# sy88932l_sampler.net
KiCad netlist of a schematic drawn in EAGLE
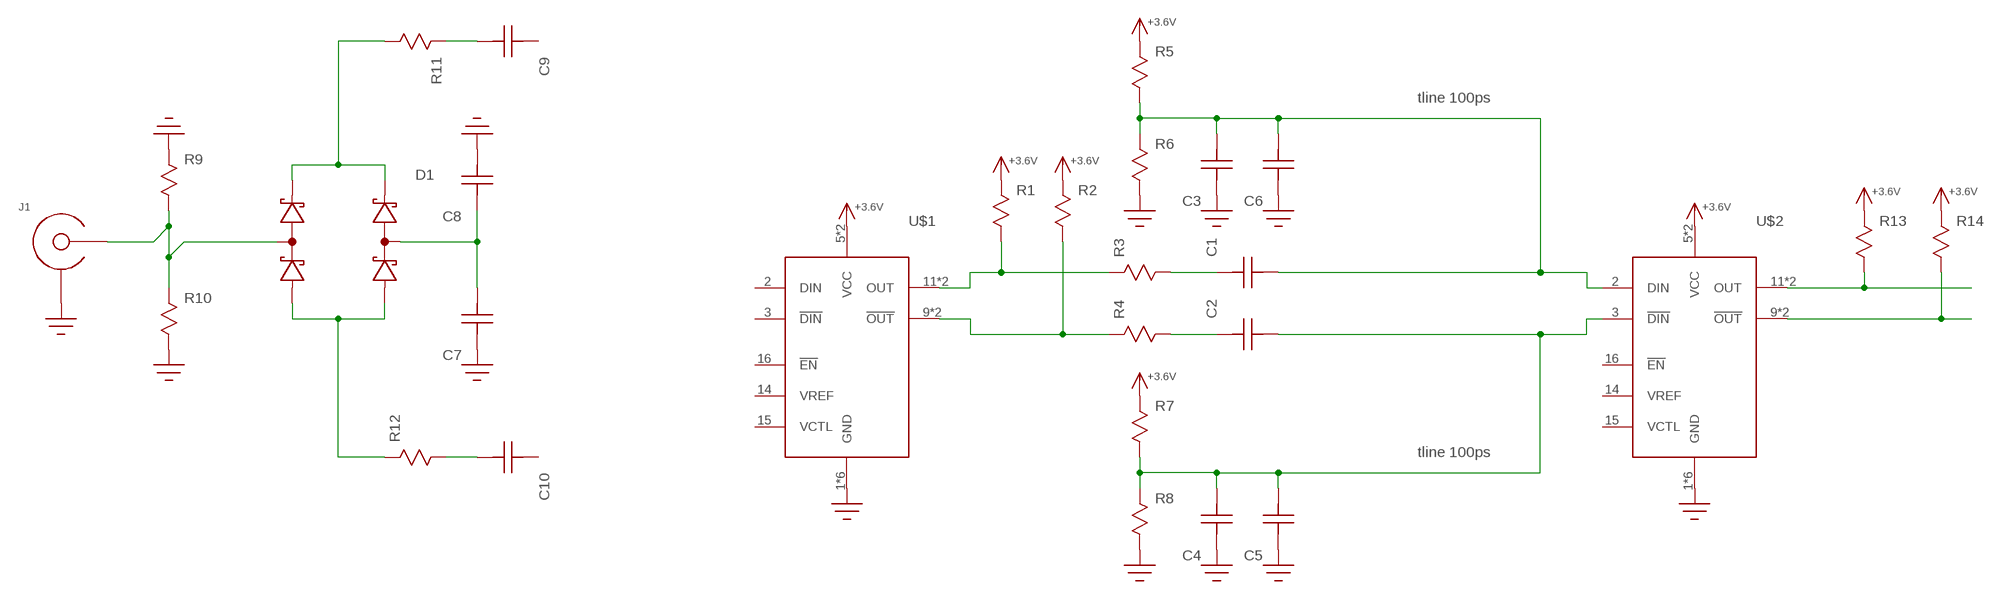
[diagram p0: schematic, sheet 1]

(export (version "E")
  (design (tool "Eeschema 10.0.6"))
  (components
    (comp (ref "C1")
      (value "C0603")
      (footprint "eagle-import:C0603")
      (libsource (lib "eagle-import") (part "C0603"))
    )
    (comp (ref "C2")
      (value "C0603")
      (footprint "eagle-import:C0603")
      (libsource (lib "eagle-import") (part "C0603"))
    )
    (comp (ref "C3")
      (value "C0603")
      (footprint "eagle-import:C0603")
      (libsource (lib "eagle-import") (part "C0603"))
    )
    (comp (ref "C4")
      (value "C0603")
      (footprint "eagle-import:C0603")
      (libsource (lib "eagle-import") (part "C0603"))
    )
    (comp (ref "C5") (value "C") (footprint "eagle-import:C0402") (libsource (lib "eagle-import") (part "C")))
    (comp (ref "C6") (value "C") (footprint "eagle-import:C0402") (libsource (lib "eagle-import") (part "C")))
    (comp (ref "C7") (value "C") (footprint "eagle-import:C0402") (libsource (lib "eagle-import") (part "C")))
    (comp (ref "C8") (value "C") (footprint "eagle-import:C0402") (libsource (lib "eagle-import") (part "C")))
    (comp (ref "C9") (value "C") (footprint "eagle-import:C0402") (libsource (lib "eagle-import") (part "C")))
    (comp (ref "C10")
      (value "C")
      (footprint "eagle-import:C0402")
      (libsource (lib "eagle-import") (part "C"))
    )
    (comp (ref "D1")
      (value "SMS3923-081")
      (footprint "eagle-import:SC-88")
      (libsource (lib "eagle-import") (part "SMS3923-081"))
    )
    (comp (ref "J1")
      (value "SMA_END_LAUNCH4L")
      (footprint "eagle-import:SMA_EDGE_LAUNCH")
      (libsource (lib "eagle-import") (part "SMA_END_LAUNCH4L"))
    )
    (comp (ref "R1")
      (value "R0603")
      (footprint "eagle-import:R0603")
      (libsource (lib "eagle-import") (part "R0603"))
    )
    (comp (ref "R2")
      (value "R0603")
      (footprint "eagle-import:R0603")
      (libsource (lib "eagle-import") (part "R0603"))
    )
    (comp (ref "R3")
      (value "R0603")
      (footprint "eagle-import:R0603")
      (libsource (lib "eagle-import") (part "R0603"))
    )
    (comp (ref "R4")
      (value "R0603")
      (footprint "eagle-import:R0603")
      (libsource (lib "eagle-import") (part "R0603"))
    )
    (comp (ref "R5")
      (value "R0603")
      (footprint "eagle-import:R0603")
      (libsource (lib "eagle-import") (part "R0603"))
    )
    (comp (ref "R6")
      (value "R0603")
      (footprint "eagle-import:R0603")
      (libsource (lib "eagle-import") (part "R0603"))
    )
    (comp (ref "R7")
      (value "R0603")
      (footprint "eagle-import:R0603")
      (libsource (lib "eagle-import") (part "R0603"))
    )
    (comp (ref "R8")
      (value "R0603")
      (footprint "eagle-import:R0603")
      (libsource (lib "eagle-import") (part "R0603"))
    )
    (comp (ref "R9")
      (value "R0603")
      (footprint "eagle-import:R0603")
      (libsource (lib "eagle-import") (part "R0603"))
    )
    (comp (ref "R10")
      (value "R0603")
      (footprint "eagle-import:R0603")
      (libsource (lib "eagle-import") (part "R0603"))
    )
    (comp (ref "R11")
      (value "R0603")
      (footprint "eagle-import:R0603")
      (libsource (lib "eagle-import") (part "R0603"))
    )
    (comp (ref "R12")
      (value "R0603")
      (footprint "eagle-import:R0603")
      (libsource (lib "eagle-import") (part "R0603"))
    )
    (comp (ref "R13")
      (value "R0603")
      (footprint "eagle-import:R0603")
      (libsource (lib "eagle-import") (part "R0603"))
    )
    (comp (ref "R14")
      (value "R0603")
      (footprint "eagle-import:R0603")
      (libsource (lib "eagle-import") (part "R0603"))
    )
    (comp (ref "U$1")
      (value "SY88932L")
      (footprint "eagle-import:TQFN16")
      (libsource (lib "eagle-import") (part "SY88932L"))
    )
    (comp (ref "U$2")
      (value "SY88932L")
      (footprint "eagle-import:TQFN16")
      (libsource (lib "eagle-import") (part "SY88932L"))
    )
  )
  (nets
    (net (code "1") (name "+3.6V") (class "Default")
      (node (ref "R1") (pin "P$1") (pinfunction "P$3_P$1") (pintype "bidirectional"))
      (node (ref "R13") (pin "P$1") (pinfunction "P$3_P$1") (pintype "bidirectional"))
      (node (ref "R14") (pin "P$1") (pinfunction "P$3_P$1") (pintype "bidirectional"))
      (node (ref "R2") (pin "P$1") (pinfunction "P$3_P$1") (pintype "bidirectional"))
      (node (ref "R5") (pin "P$1") (pinfunction "P$3_P$1") (pintype "bidirectional"))
      (node (ref "R7") (pin "P$1") (pinfunction "P$3_P$1") (pintype "bidirectional"))
      (node (ref "U$1") (pin "5") (pinfunction "VCC_5") (pintype "bidirectional"))
      (node (ref "U$1") (pin "6") (pinfunction "VCC_6") (pintype "bidirectional"))
      (node (ref "U$2") (pin "5") (pinfunction "VCC_5") (pintype "bidirectional"))
      (node (ref "U$2") (pin "6") (pinfunction "VCC_6") (pintype "bidirectional"))
    )
    (net (code "2") (name "GND") (class "Default")
      (node (ref "C3") (pin "P$2") (pinfunction "P$2_P$2") (pintype "bidirectional"))
      (node (ref "C4") (pin "P$2") (pinfunction "P$2_P$2") (pintype "bidirectional"))
      (node (ref "C5") (pin "2") (pinfunction "P$2_2") (pintype "bidirectional"))
      (node (ref "C6") (pin "2") (pinfunction "P$2_2") (pintype "bidirectional"))
      (node (ref "C7") (pin "2") (pinfunction "P$2_2") (pintype "bidirectional"))
      (node (ref "C8") (pin "1") (pinfunction "P$1_1") (pintype "bidirectional"))
      (node (ref "J1") (pin "BOTTOM_PAD") (pinfunction "SHIELD_BOTTOM_PAD") (pintype "bidirectional"))
      (node (ref "J1") (pin "GND@1") (pinfunction "SHIELD_GND@1") (pintype "bidirectional"))
      (node (ref "J1") (pin "GND@14") (pinfunction "SHIELD_GND@14") (pintype "bidirectional"))
      (node (ref "J1") (pin "GND@15") (pinfunction "SHIELD_GND@15") (pintype "bidirectional"))
      (node (ref "J1") (pin "GND@16") (pinfunction "SHIELD_GND@16") (pintype "bidirectional"))
      (node (ref "J1") (pin "GND@17") (pinfunction "SHIELD_GND@17") (pintype "bidirectional"))
      (node (ref "J1") (pin "GND@2") (pinfunction "SHIELD_GND@2") (pintype "bidirectional"))
      (node (ref "J1") (pin "GND@3") (pinfunction "SHIELD_GND@3") (pintype "bidirectional"))
      (node (ref "J1") (pin "GND@4") (pinfunction "SHIELD_GND@4") (pintype "bidirectional"))
      (node (ref "J1") (pin "GND@5") (pinfunction "SHIELD_GND@5") (pintype "bidirectional"))
      (node (ref "J1") (pin "GND@6") (pinfunction "SHIELD_GND@6") (pintype "bidirectional"))
      (node (ref "J1") (pin "GND@7") (pinfunction "SHIELD_GND@7") (pintype "bidirectional"))
      (node (ref "J1") (pin "GND@8") (pinfunction "SHIELD_GND@8") (pintype "bidirectional"))
      (node (ref "J1") (pin "GND_PAD1") (pinfunction "SHIELD_GND_PAD1") (pintype "bidirectional"))
      (node (ref "J1") (pin "GND_PAD2") (pinfunction "SHIELD_GND_PAD2") (pintype "bidirectional"))
      (node (ref "R10") (pin "P$2") (pinfunction "P$4_P$2") (pintype "bidirectional"))
      (node (ref "R6") (pin "P$2") (pinfunction "P$4_P$2") (pintype "bidirectional"))
      (node (ref "R8") (pin "P$2") (pinfunction "P$4_P$2") (pintype "bidirectional"))
      (node (ref "R9") (pin "P$1") (pinfunction "P$3_P$1") (pintype "bidirectional"))
      (node (ref "U$1") (pin "1") (pinfunction "GND_1") (pintype "bidirectional"))
      (node (ref "U$1") (pin "13") (pinfunction "GND_13") (pintype "bidirectional"))
      (node (ref "U$1") (pin "4") (pinfunction "GND_4") (pintype "bidirectional"))
      (node (ref "U$1") (pin "7") (pinfunction "GND_7") (pintype "bidirectional"))
      (node (ref "U$1") (pin "8") (pinfunction "GND_8") (pintype "bidirectional"))
      (node (ref "U$1") (pin "EP") (pinfunction "GND_EP") (pintype "bidirectional"))
      (node (ref "U$2") (pin "1") (pinfunction "GND_1") (pintype "bidirectional"))
      (node (ref "U$2") (pin "13") (pinfunction "GND_13") (pintype "bidirectional"))
      (node (ref "U$2") (pin "4") (pinfunction "GND_4") (pintype "bidirectional"))
      (node (ref "U$2") (pin "7") (pinfunction "GND_7") (pintype "bidirectional"))
      (node (ref "U$2") (pin "8") (pinfunction "GND_8") (pintype "bidirectional"))
      (node (ref "U$2") (pin "EP") (pinfunction "GND_EP") (pintype "bidirectional"))
    )
    (net (code "3") (name "Net-(C5-P$1)") (class "Default")
      (node (ref "C2") (pin "P$1") (pinfunction "P$1_P$1") (pintype "bidirectional"))
      (node (ref "C4") (pin "P$1") (pinfunction "P$1_P$1") (pintype "bidirectional"))
      (node (ref "C5") (pin "1") (pinfunction "P$1_1") (pintype "bidirectional"))
      (node (ref "R7") (pin "P$2") (pinfunction "P$4_P$2") (pintype "bidirectional"))
      (node (ref "R8") (pin "P$1") (pinfunction "P$3_P$1") (pintype "bidirectional"))
      (node (ref "U$2") (pin "3") (pinfunction "~{DIN}_3") (pintype "bidirectional"))
    )
    (net (code "4") (name "Net-(C6-P$1)") (class "Default")
      (node (ref "C1") (pin "P$1") (pinfunction "P$1_P$1") (pintype "bidirectional"))
      (node (ref "C3") (pin "P$1") (pinfunction "P$1_P$1") (pintype "bidirectional"))
      (node (ref "C6") (pin "1") (pinfunction "P$1_1") (pintype "bidirectional"))
      (node (ref "R5") (pin "P$2") (pinfunction "P$4_P$2") (pintype "bidirectional"))
      (node (ref "R6") (pin "P$1") (pinfunction "P$3_P$1") (pintype "bidirectional"))
      (node (ref "U$2") (pin "2") (pinfunction "DIN_2") (pintype "bidirectional"))
    )
    (net (code "5") (name "Net-(C7-P$1)") (class "Default")
      (node (ref "C7") (pin "1") (pinfunction "P$1_1") (pintype "bidirectional"))
      (node (ref "C8") (pin "2") (pinfunction "P$2_2") (pintype "bidirectional"))
      (node (ref "D1") (pin "2") (pinfunction "COMMON0_2") (pintype "bidirectional"))
    )
    (net (code "6") (name "Net-(C9-P$1)") (class "Default")
      (node (ref "C9") (pin "1") (pinfunction "P$1_1") (pintype "bidirectional"))
      (node (ref "R11") (pin "P$1") (pinfunction "P$3_P$1") (pintype "bidirectional"))
    )
    (net (code "7") (name "Net-(C10-P$1)") (class "Default")
      (node (ref "C10") (pin "1") (pinfunction "P$1_1") (pintype "bidirectional"))
      (node (ref "R12") (pin "P$2") (pinfunction "P$4_P$2") (pintype "bidirectional"))
    )
    (net (code "8") (name "Net-(D1-ANODE0)") (class "Default")
      (node (ref "D1") (pin "1") (pinfunction "ANODE0_1") (pintype "bidirectional"))
      (node (ref "D1") (pin "6") (pinfunction "ANODE1_6") (pintype "bidirectional"))
      (node (ref "R12") (pin "P$1") (pinfunction "P$3_P$1") (pintype "bidirectional"))
    )
    (net (code "9") (name "Net-(D1-CATHODE0)") (class "Default")
      (node (ref "D1") (pin "3") (pinfunction "CATHODE0_3") (pintype "bidirectional"))
      (node (ref "D1") (pin "4") (pinfunction "CATHODE1_4") (pintype "bidirectional"))
      (node (ref "R11") (pin "P$2") (pinfunction "P$4_P$2") (pintype "bidirectional"))
    )
    (net (code "10") (name "Net-(D1-COMMON1)") (class "Default")
      (node (ref "D1") (pin "5") (pinfunction "COMMON1_5") (pintype "bidirectional"))
      (node (ref "J1") (pin "CENTER@1") (pinfunction "CENTER_CENTER@1") (pintype "bidirectional"))
      (node (ref "J1") (pin "CENTER@2") (pinfunction "CENTER_CENTER@2") (pintype "bidirectional"))
      (node (ref "R10") (pin "P$1") (pinfunction "P$3_P$1") (pintype "bidirectional"))
      (node (ref "R9") (pin "P$2") (pinfunction "P$4_P$2") (pintype "bidirectional"))
    )
    (net (code "11") (name "Net-(R1-P$4)") (class "Default")
      (node (ref "R1") (pin "P$2") (pinfunction "P$4_P$2") (pintype "bidirectional"))
      (node (ref "R3") (pin "P$1") (pinfunction "P$3_P$1") (pintype "bidirectional"))
      (node (ref "U$1") (pin "11") (pinfunction "OUT_11") (pintype "bidirectional"))
      (node (ref "U$1") (pin "12") (pinfunction "OUT_12") (pintype "bidirectional"))
    )
    (net (code "12") (name "Net-(R2-P$4)") (class "Default")
      (node (ref "R2") (pin "P$2") (pinfunction "P$4_P$2") (pintype "bidirectional"))
      (node (ref "R4") (pin "P$1") (pinfunction "P$3_P$1") (pintype "bidirectional"))
      (node (ref "U$1") (pin "10") (pinfunction "~{OUT}_10") (pintype "bidirectional"))
      (node (ref "U$1") (pin "9") (pinfunction "~{OUT}_9") (pintype "bidirectional"))
    )
    (net (code "13") (name "Net-(R3-P$4)") (class "Default")
      (node (ref "C1") (pin "P$2") (pinfunction "P$2_P$2") (pintype "bidirectional"))
      (node (ref "R3") (pin "P$2") (pinfunction "P$4_P$2") (pintype "bidirectional"))
    )
    (net (code "14") (name "Net-(R4-P$4)") (class "Default")
      (node (ref "C2") (pin "P$2") (pinfunction "P$2_P$2") (pintype "bidirectional"))
      (node (ref "R4") (pin "P$2") (pinfunction "P$4_P$2") (pintype "bidirectional"))
    )
    (net (code "15") (name "Net-(R13-P$4)") (class "Default")
      (node (ref "R13") (pin "P$2") (pinfunction "P$4_P$2") (pintype "bidirectional"))
      (node (ref "U$2") (pin "11") (pinfunction "OUT_11") (pintype "bidirectional"))
      (node (ref "U$2") (pin "12") (pinfunction "OUT_12") (pintype "bidirectional"))
    )
    (net (code "16") (name "Net-(R14-P$4)") (class "Default")
      (node (ref "R14") (pin "P$2") (pinfunction "P$4_P$2") (pintype "bidirectional"))
      (node (ref "U$2") (pin "10") (pinfunction "~{OUT}_10") (pintype "bidirectional"))
      (node (ref "U$2") (pin "9") (pinfunction "~{OUT}_9") (pintype "bidirectional"))
    )
    (net (code "17") (name "unconnected-(C9-P$2-Pad2)") (class "Default")
      (node (ref "C9") (pin "2") (pinfunction "P$2_2") (pintype "bidirectional"))
    )
    (net (code "18") (name "unconnected-(C10-P$2-Pad2)") (class "Default")
      (node (ref "C10") (pin "2") (pinfunction "P$2_2") (pintype "bidirectional"))
    )
    (net (code "19") (name "unconnected-(U$1-DIN-Pad2)") (class "Default")
      (node (ref "U$1") (pin "2") (pinfunction "DIN_2") (pintype "bidirectional"))
    )
    (net (code "20") (name "unconnected-(U$1-VCTL-Pad15)") (class "Default")
      (node (ref "U$1") (pin "15") (pinfunction "VCTL_15") (pintype "bidirectional"))
    )
    (net (code "21") (name "unconnected-(U$1-VREF-Pad14)") (class "Default")
      (node (ref "U$1") (pin "14") (pinfunction "VREF_14") (pintype "bidirectional"))
    )
    (net (code "22") (name "unconnected-(U$1-~{DIN}-Pad3)") (class "Default")
      (node (ref "U$1") (pin "3") (pinfunction "~{DIN}_3") (pintype "bidirectional"))
    )
    (net (code "23") (name "unconnected-(U$1-~{EN}-Pad16)") (class "Default")
      (node (ref "U$1") (pin "16") (pinfunction "~{EN}_16") (pintype "bidirectional"))
    )
    (net (code "24") (name "unconnected-(U$2-VCTL-Pad15)") (class "Default")
      (node (ref "U$2") (pin "15") (pinfunction "VCTL_15") (pintype "bidirectional"))
    )
    (net (code "25") (name "unconnected-(U$2-VREF-Pad14)") (class "Default")
      (node (ref "U$2") (pin "14") (pinfunction "VREF_14") (pintype "bidirectional"))
    )
    (net (code "26") (name "unconnected-(U$2-~{EN}-Pad16)") (class "Default")
      (node (ref "U$2") (pin "16") (pinfunction "~{EN}_16") (pintype "bidirectional"))
    )
  )
)
